# LNA_1_7GHz_first_stage.net
KiCad netlist of a schematic drawn in Altium Designer
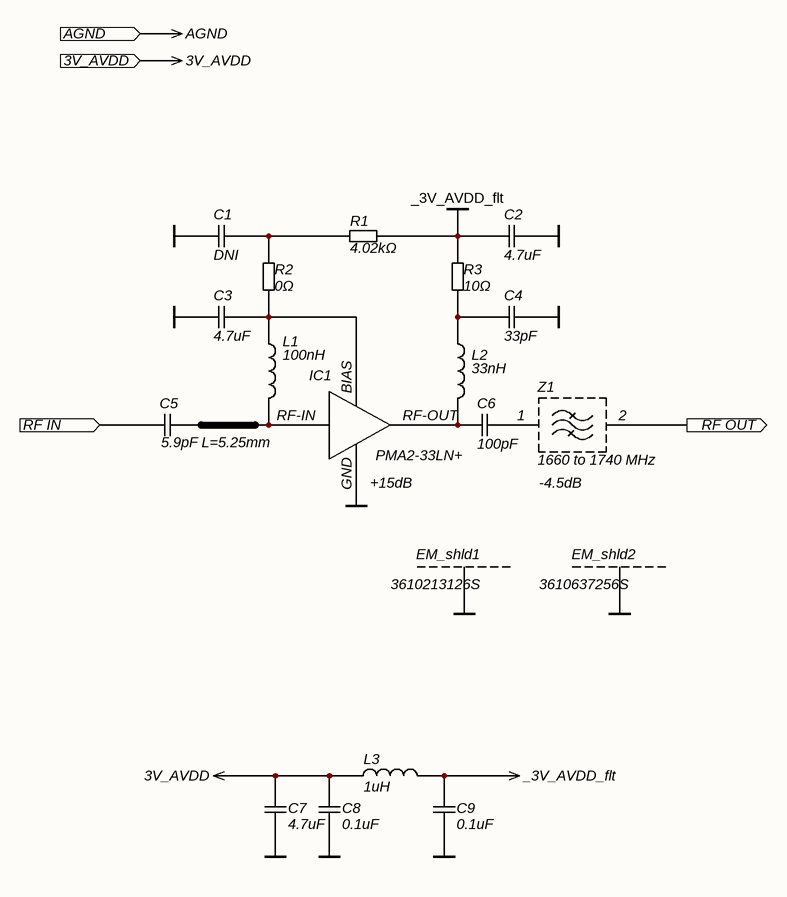
[diagram p0: LNA_1.7GHz_first_stage.SchDoc]

(export (version "E")
  (design (tool "Eeschema 10.0.6"))
  (components
    (comp (ref "C1")
      (value "DNI")
      (footprint "LNA_1.7GHz:C0603")
      (description "Керамический конденсатор")
      (libsource (lib "LNA_1.7GHz") (part "CAP"))
    )
    (comp (ref "C2")
      (value "4.7uF")
      (footprint "LNA_1.7GHz:C0603")
      (description "Керамический конденсатор")
      (libsource (lib "LNA_1.7GHz") (part "CAP"))
    )
    (comp (ref "C3")
      (value "4.7uF")
      (footprint "LNA_1.7GHz:C0603")
      (description "Керамический конденсатор")
      (libsource (lib "LNA_1.7GHz") (part "CAP"))
    )
    (comp (ref "C4")
      (value "33pF")
      (footprint "LNA_1.7GHz:C0603")
      (description "Керамический конденсатор")
      (libsource (lib "LNA_1.7GHz") (part "CAP"))
    )
    (comp (ref "C5")
      (value "5.9pF")
      (footprint "LNA_1.7GHz:C0603")
      (description "Керамический конденсатор")
      (libsource (lib "LNA_1.7GHz") (part "CAP"))
    )
    (comp (ref "C6")
      (value "100pF")
      (footprint "LNA_1.7GHz:C0603")
      (description "Керамический конденсатор")
      (libsource (lib "LNA_1.7GHz") (part "CAP"))
    )
    (comp (ref "C7")
      (value "4.7uF")
      (footprint "LNA_1.7GHz:C0603")
      (description "Керамический конденсатор")
      (libsource (lib "LNA_1.7GHz") (part "CAP"))
    )
    (comp (ref "C8")
      (value "0.1uF")
      (footprint "LNA_1.7GHz:C0603")
      (description "Керамический конденсатор")
      (libsource (lib "LNA_1.7GHz") (part "CAP"))
    )
    (comp (ref "C9")
      (value "0.1uF")
      (footprint "LNA_1.7GHz:C0603")
      (description "Керамический конденсатор")
      (libsource (lib "LNA_1.7GHz") (part "CAP"))
    )
    (comp (ref "EM_shld1")
      (value "3610213126S")
      (footprint "WE-SHC:3610213126S")
      (description "RF Shield Frame X 0.522\" (13.26mm) Surface Mount")
      (libsource (lib "LNA_1.7GHz") (part "RF Shield"))
    )
    (comp (ref "EM_shld2")
      (value "3610637256S")
      (footprint "WE-SHC:3610637256S")
      (description "RF Shield Frame X 1.484\" (37.70mm) Surface Mount")
      (libsource (lib "LNA_1.7GHz") (part "RF Shield"))
    )
    (comp (ref "IC1")
      (value "PMA2-33LN+")
      (footprint "LNA_1.7GHz:MC1631-1_MNC-L")
      (description "Малошумяший усилитель")
      (libsource (lib "LNA_1.7GHz") (part "PMA2-33LN+"))
    )
    (comp (ref "L1")
      (value "100nH")
      (footprint "LNA_1.7GHz:L0603_HP")
      (description "Индуктивность")
      (libsource (lib "LNA_1.7GHz") (part "Inducror RF"))
    )
    (comp (ref "L2")
      (value "33nH")
      (footprint "LNA_1.7GHz:L0603_HP")
      (description "Индуктивность")
      (libsource (lib "LNA_1.7GHz") (part "Inducror RF"))
    )
    (comp (ref "L3")
      (value "1uH")
      (footprint "Kintex_SDR:L1206_Murata")
      (description "Индуктивность")
      (libsource (lib "LNA_1.7GHz") (part "Inducror LF"))
    )
    (comp (ref "R1")
      (value "4.02kΩ")
      (footprint "LNA_1.7GHz:R0603")
      (description "SMD резистор")
      (libsource (lib "LNA_1.7GHz") (part "RES"))
    )
    (comp (ref "R2")
      (value "0Ω")
      (footprint "LNA_1.7GHz:R0603")
      (description "SMD резистор")
      (libsource (lib "") (part "RES_1"))
    )
    (comp (ref "R3")
      (value "10Ω")
      (footprint "LNA_1.7GHz:R0603")
      (description "SMD резистор")
      (libsource (lib "") (part "RES_1"))
    )
    (comp (ref "Z1")
      (value "1660 to 1740 MHz")
      (footprint "LNA_1.7GHz:BPF_1700MHz_10.2_635um")
      (description "Полосковый фильтр")
      (libsource (lib "LNA_1.7GHz") (part "BPF_1700MHz"))
    )
  )
  (nets
    (net (code "1") (name "/RF IN") (class "Default")
      (node (ref "C5") (pin "1") (pinfunction "1_1") (pintype "passive"))
    )
    (net (code "2") (name "/RF OUT") (class "Default")
      (node (ref "Z1") (pin "2") (pinfunction "2_2") (pintype "passive"))
    )
    (net (code "3") (name "3V_AVDD") (class "Default")
      (node (ref "C7") (pin "2") (pinfunction "2_2") (pintype "passive"))
      (node (ref "C8") (pin "2") (pinfunction "2_2") (pintype "passive"))
      (node (ref "L3") (pin "2") (pinfunction "2_2") (pintype "passive"))
    )
    (net (code "4") (name "AGND") (class "Default")
      (node (ref "C1") (pin "1") (pinfunction "1_1") (pintype "passive"))
      (node (ref "C2") (pin "2") (pinfunction "2_2") (pintype "passive"))
      (node (ref "C3") (pin "1") (pinfunction "1_1") (pintype "passive"))
      (node (ref "C4") (pin "2") (pinfunction "2_2") (pintype "passive"))
      (node (ref "C7") (pin "1") (pinfunction "1_1") (pintype "passive"))
      (node (ref "C8") (pin "1") (pinfunction "1_1") (pintype "passive"))
      (node (ref "C9") (pin "1") (pinfunction "1_1") (pintype "passive"))
      (node (ref "EM_shld1") (pin "1") (pinfunction "1_1") (pintype "passive"))
      (node (ref "EM_shld2") (pin "1") (pinfunction "1_1") (pintype "passive"))
      (node (ref "IC1") (pin "GND") (pinfunction "GND_GND") (pintype "passive"))
    )
    (net (code "5") (name "Net-(C1-Pad2)") (class "Default")
      (node (ref "C1") (pin "2") (pinfunction "2_2") (pintype "passive"))
      (node (ref "R1") (pin "2") (pinfunction "2_2") (pintype "passive"))
      (node (ref "R2") (pin "2") (pinfunction "2_2") (pintype "passive"))
    )
    (net (code "6") (name "Net-(C3-Pad2)") (class "Default")
      (node (ref "C3") (pin "2") (pinfunction "2_2") (pintype "passive"))
      (node (ref "IC1") (pin "BIAS") (pinfunction "BIAS_BIAS") (pintype "passive"))
      (node (ref "L1") (pin "1") (pinfunction "1_1") (pintype "passive"))
      (node (ref "R2") (pin "1") (pinfunction "1_1") (pintype "passive"))
    )
    (net (code "7") (name "Net-(C4-Pad1)") (class "Default")
      (node (ref "C4") (pin "1") (pinfunction "1_1") (pintype "passive"))
      (node (ref "L2") (pin "1") (pinfunction "1_1") (pintype "passive"))
      (node (ref "R3") (pin "1") (pinfunction "1_1") (pintype "passive"))
    )
    (net (code "8") (name "Net-(C5-Pad2)") (class "Default")
      (node (ref "C5") (pin "2") (pinfunction "2_2") (pintype "passive"))
      (node (ref "IC1") (pin "RF-IN") (pinfunction "RF-IN_RF-IN") (pintype "passive"))
      (node (ref "L1") (pin "2") (pinfunction "2_2") (pintype "passive"))
    )
    (net (code "9") (name "Net-(C6-Pad1)") (class "Default")
      (node (ref "C6") (pin "1") (pinfunction "1_1") (pintype "passive"))
      (node (ref "IC1") (pin "RF-OUT") (pinfunction "RF-OUT_RF-OUT") (pintype "passive"))
      (node (ref "L2") (pin "2") (pinfunction "2_2") (pintype "passive"))
    )
    (net (code "10") (name "Net-(C6-Pad2)") (class "Default")
      (node (ref "C6") (pin "2") (pinfunction "2_2") (pintype "passive"))
      (node (ref "Z1") (pin "1") (pinfunction "1_1") (pintype "passive"))
    )
    (net (code "11") (name "_3V_AVDD_flt") (class "Default")
      (node (ref "C2") (pin "1") (pinfunction "1_1") (pintype "passive"))
      (node (ref "C9") (pin "2") (pinfunction "2_2") (pintype "passive"))
      (node (ref "L3") (pin "1") (pinfunction "1_1") (pintype "passive"))
      (node (ref "R1") (pin "1") (pinfunction "1_1") (pintype "passive"))
      (node (ref "R3") (pin "2") (pinfunction "2_2") (pintype "passive"))
    )
  )
)
